# 3rd_eyes.net
KiCad netlist of a schematic drawn in Altium Designer
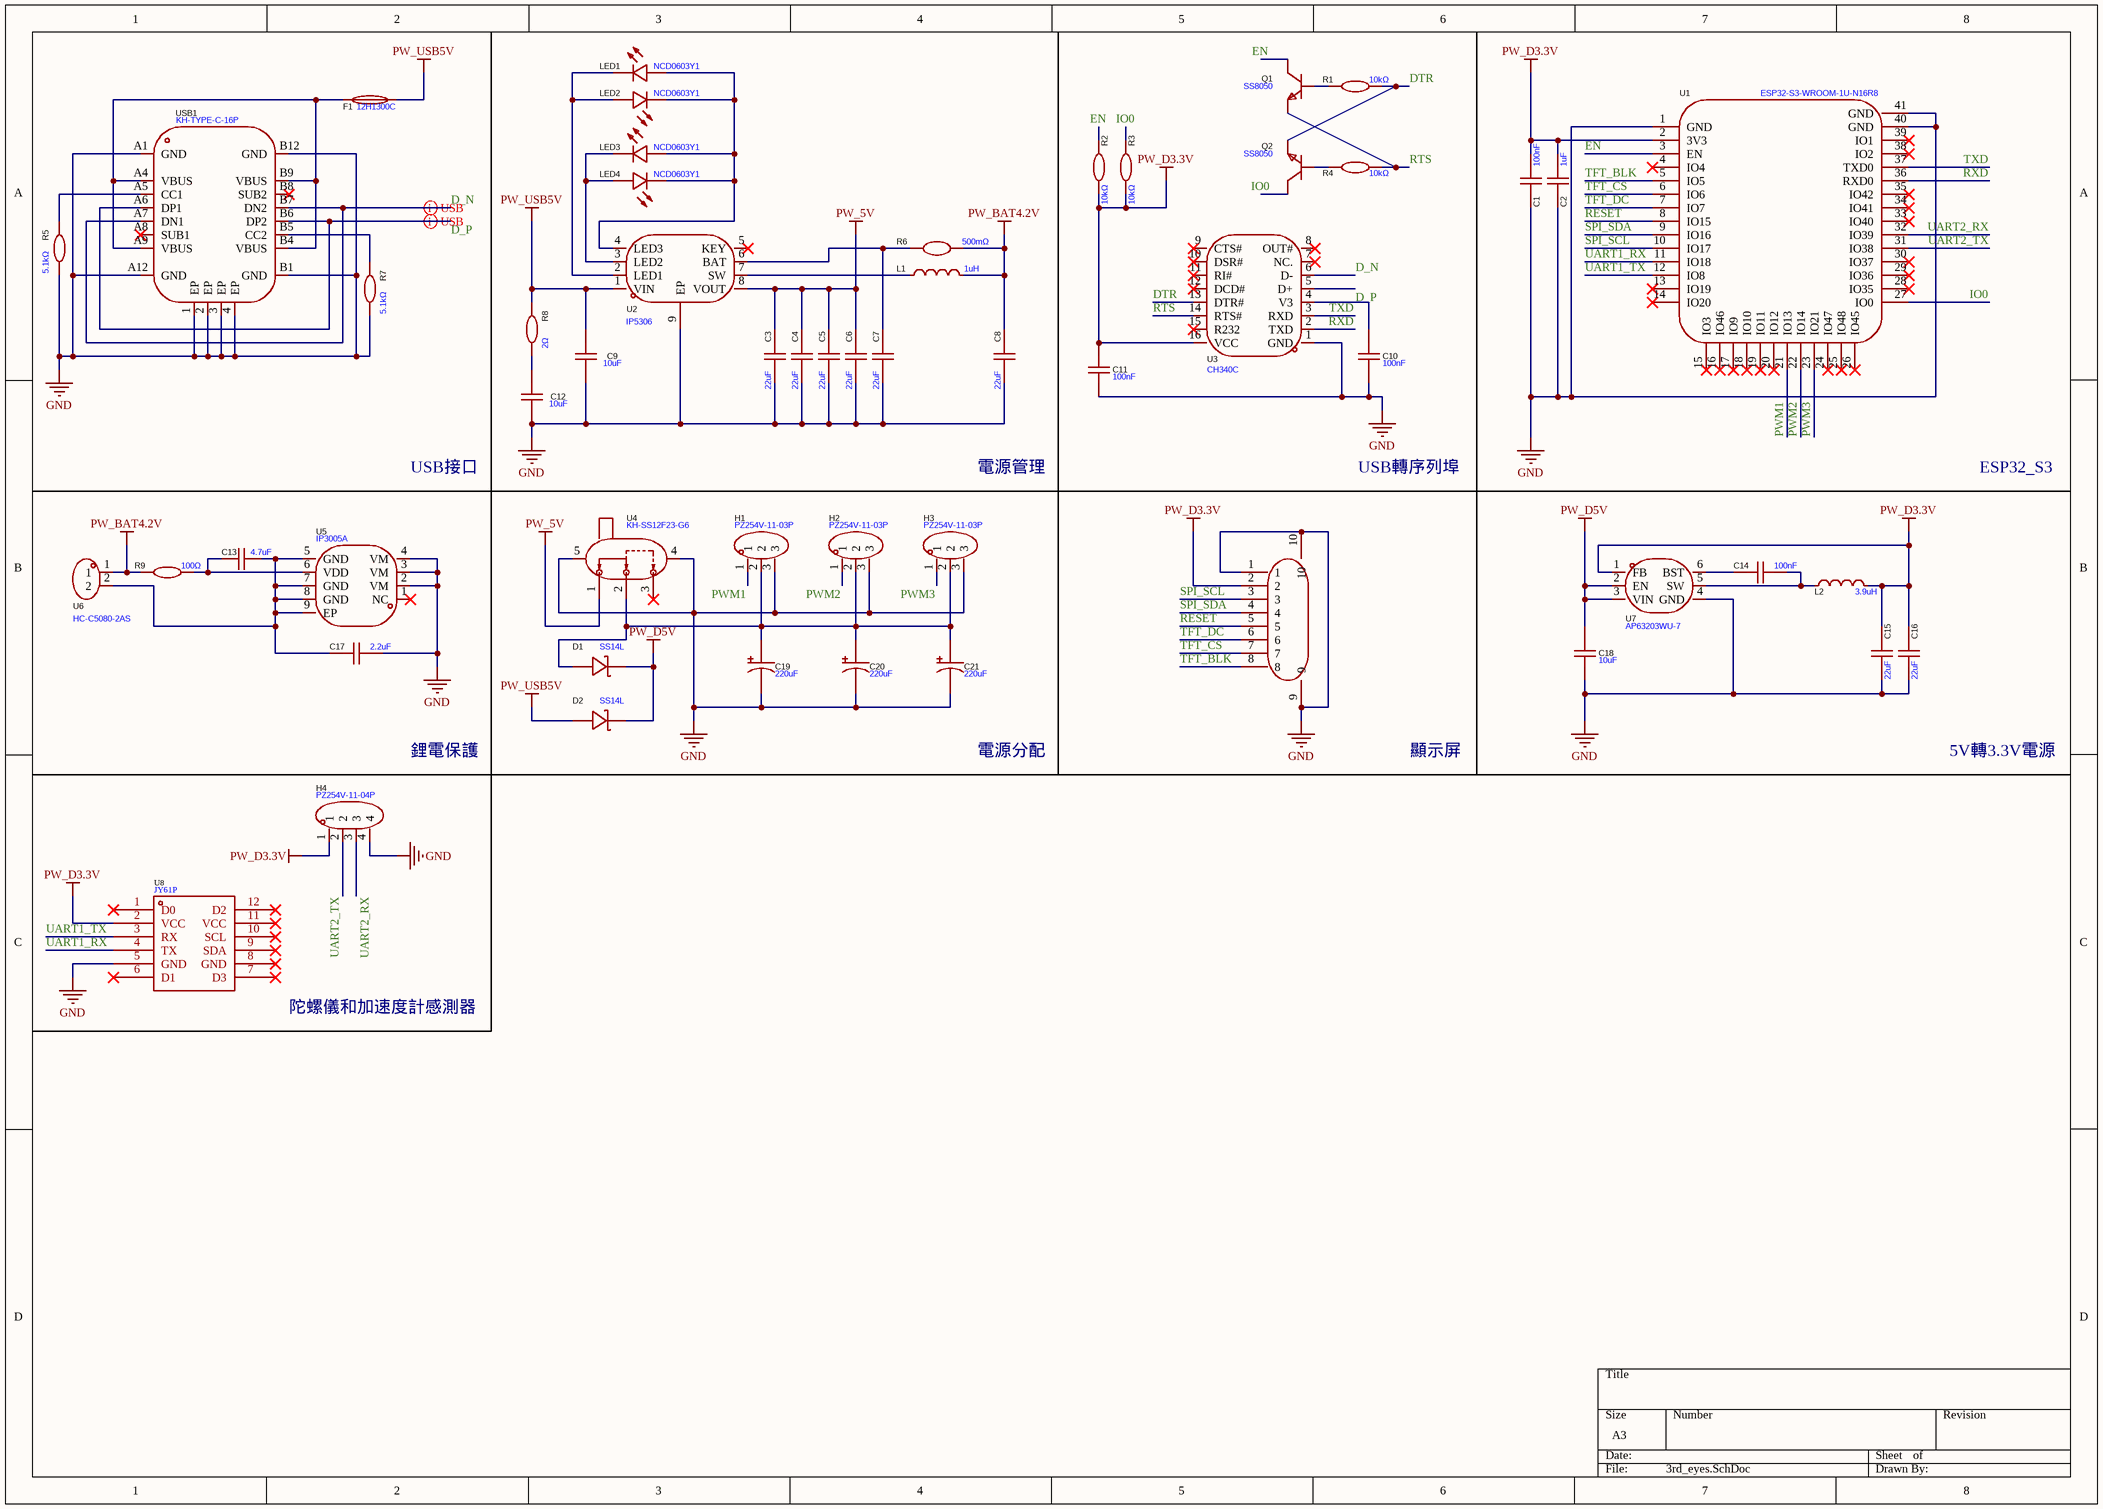
[diagram p0: 3rd_eyes.SchDoc]

(export (version "E")
  (design (tool "Eeschema 10.0.6"))
  (components
    (comp (ref "C1")
      (value "100nF")
      (footprint "C0603")
      (fields
        (field (name "MANUFACTURER") "SAMSUNG(三星)")
        (field (name "MANUFACTURER PART") "CL10B104KB8NNNC")
        (field (name "TOLERANCE") "±10%")
      )
      (libsource (lib "電容") (part "CL10B104KB8NNNC"))
    )
    (comp (ref "C2")
      (value "1uF")
      (footprint "C0603")
      (fields
        (field (name "MANUFACTURER") "SAMSUNG(三星)")
        (field (name "MANUFACTURER PART") "CL10A105KB8NNNC")
        (field (name "TOLERANCE") "±10%")
      )
      (libsource (lib "電容") (part "CL10A105KB8NNNC"))
    )
    (comp (ref "C3")
      (value "22uF")
      (footprint "C0805")
      (fields
        (field (name "MANUFACTURER") "SAMSUNG(三星)")
        (field (name "MANUFACTURER PART") "CL21A226MAQNNNE")
        (field (name "TOLERANCE") "±20%")
      )
      (libsource (lib "電容") (part "CL21A226MAQNNNE"))
    )
    (comp (ref "C4")
      (value "22uF")
      (footprint "C0805")
      (fields
        (field (name "MANUFACTURER") "SAMSUNG(三星)")
        (field (name "MANUFACTURER PART") "CL21A226MAQNNNE")
        (field (name "TOLERANCE") "±20%")
      )
      (libsource (lib "電容") (part "CL21A226MAQNNNE"))
    )
    (comp (ref "C5")
      (value "22uF")
      (footprint "C0805")
      (fields
        (field (name "MANUFACTURER") "SAMSUNG(三星)")
        (field (name "MANUFACTURER PART") "CL21A226MAQNNNE")
        (field (name "TOLERANCE") "±20%")
      )
      (libsource (lib "電容") (part "CL21A226MAQNNNE"))
    )
    (comp (ref "C6")
      (value "22uF")
      (footprint "C0805")
      (fields
        (field (name "MANUFACTURER") "SAMSUNG(三星)")
        (field (name "MANUFACTURER PART") "CL21A226MAQNNNE")
        (field (name "TOLERANCE") "±20%")
      )
      (libsource (lib "電容") (part "CL21A226MAQNNNE"))
    )
    (comp (ref "C7")
      (value "22uF")
      (footprint "C0805")
      (fields
        (field (name "MANUFACTURER") "SAMSUNG(三星)")
        (field (name "MANUFACTURER PART") "CL21A226MAQNNNE")
        (field (name "TOLERANCE") "±20%")
      )
      (libsource (lib "電容") (part "CL21A226MAQNNNE"))
    )
    (comp (ref "C8")
      (value "22uF")
      (footprint "C0805")
      (fields
        (field (name "MANUFACTURER") "SAMSUNG(三星)")
        (field (name "MANUFACTURER PART") "CL21A226MAQNNNE")
        (field (name "TOLERANCE") "±20%")
      )
      (libsource (lib "電容") (part "CL21A226MAQNNNE"))
    )
    (comp (ref "C9")
      (value "10uF")
      (footprint "C0603")
      (fields
        (field (name "MANUFACTURER") "SAMSUNG(三星)")
        (field (name "MANUFACTURER PART") "CL10A106MA8NRNC")
        (field (name "TOLERANCE") "±20%")
      )
      (libsource (lib "電容") (part "CL10A106MA8NRNC"))
    )
    (comp (ref "C10")
      (value "100nF")
      (footprint "C0603")
      (fields
        (field (name "MANUFACTURER") "SAMSUNG(三星)")
        (field (name "MANUFACTURER PART") "CL10B104KB8NNNC")
        (field (name "TOLERANCE") "±10%")
      )
      (libsource (lib "電容") (part "CL10B104KB8NNNC"))
    )
    (comp (ref "C11")
      (value "100nF")
      (footprint "C0603")
      (fields
        (field (name "MANUFACTURER") "SAMSUNG(三星)")
        (field (name "MANUFACTURER PART") "CL10B104KB8NNNC")
        (field (name "TOLERANCE") "±10%")
      )
      (libsource (lib "電容") (part "CL10B104KB8NNNC"))
    )
    (comp (ref "C12")
      (value "10uF")
      (footprint "C0603")
      (fields
        (field (name "MANUFACTURER") "SAMSUNG(三星)")
        (field (name "MANUFACTURER PART") "CL10A106MA8NRNC")
        (field (name "TOLERANCE") "±20%")
      )
      (libsource (lib "電容") (part "CL10A106MA8NRNC"))
    )
    (comp (ref "C13")
      (value "4.7uF")
      (footprint "C0603")
      (fields
        (field (name "MANUFACTURER") "SAMSUNG(三星)")
        (field (name "MANUFACTURER PART") "CL10A475KO8NNNC")
        (field (name "TOLERANCE") "±10%")
      )
      (libsource (lib "電容") (part "CL10A475KO8NNNC"))
    )
    (comp (ref "C14")
      (value "100nF")
      (footprint "C0603")
      (fields
        (field (name "MANUFACTURER") "SAMSUNG(三星)")
        (field (name "MANUFACTURER PART") "CL10B104KB8NNNC")
        (field (name "TOLERANCE") "±10%")
      )
      (libsource (lib "電容") (part "CL10B104KB8NNNC"))
    )
    (comp (ref "C15")
      (value "22uF")
      (footprint "C0805")
      (fields
        (field (name "MANUFACTURER") "SAMSUNG(三星)")
        (field (name "MANUFACTURER PART") "CL21A226MAQNNNE")
        (field (name "TOLERANCE") "±20%")
      )
      (libsource (lib "電容") (part "CL21A226MAQNNNE"))
    )
    (comp (ref "C16")
      (value "22uF")
      (footprint "C0805")
      (fields
        (field (name "MANUFACTURER") "SAMSUNG(三星)")
        (field (name "MANUFACTURER PART") "CL21A226MAQNNNE")
        (field (name "TOLERANCE") "±20%")
      )
      (libsource (lib "電容") (part "CL21A226MAQNNNE"))
    )
    (comp (ref "C17")
      (value "2.2uF")
      (footprint "C0603")
      (fields
        (field (name "MANUFACTURER") "SAMSUNG(三星)")
        (field (name "MANUFACTURER PART") "CL10A225KB8NNNC")
        (field (name "TOLERANCE") "±10%")
      )
      (libsource (lib "電容") (part "CL10A225KB8NNNC"))
    )
    (comp (ref "C18")
      (value "10uF")
      (footprint "C0603")
      (fields
        (field (name "MANUFACTURER") "SAMSUNG(三星)")
        (field (name "MANUFACTURER PART") "CL10A106MA8NRNC")
        (field (name "TOLERANCE") "±20%")
      )
      (libsource (lib "電容") (part "CL10A106MA8NRNC"))
    )
    (comp (ref "C19")
      (value "220uF")
      (footprint "CAP-SMD_BD6.3-L6.6-W6.6-FD-A")
      (fields
        (field (name "MANUFACTURER") "lelon(立隆)")
        (field (name "MANUFACTURER PART") "OVZ221M0JTR-0606")
        (field (name "TOLERANCE") "±20%")
      )
      (libsource (lib "電容") (part "OVZ221M0JTR-0606"))
    )
    (comp (ref "C20")
      (value "220uF")
      (footprint "CAP-SMD_BD6.3-L6.6-W6.6-FD-A")
      (fields
        (field (name "MANUFACTURER") "lelon(立隆)")
        (field (name "MANUFACTURER PART") "OVZ221M0JTR-0606")
        (field (name "TOLERANCE") "±20%")
      )
      (libsource (lib "電容") (part "OVZ221M0JTR-0606"))
    )
    (comp (ref "C21")
      (value "220uF")
      (footprint "CAP-SMD_BD6.3-L6.6-W6.6-FD-A")
      (fields
        (field (name "MANUFACTURER") "lelon(立隆)")
        (field (name "MANUFACTURER PART") "OVZ221M0JTR-0606")
        (field (name "TOLERANCE") "±20%")
      )
      (libsource (lib "電容") (part "OVZ221M0JTR-0606"))
    )
    (comp (ref "D1")
      (value "SS14L")
      (footprint "SOD-123F_L2.8-W1.8-LS3.7-RD")
      (fields (field (name "MANUFACTURER") "Hottech(合科泰)"))
      (libsource (lib "二極管") (part "SS14L"))
    )
    (comp (ref "D2")
      (value "SS14L")
      (footprint "SOD-123F_L2.8-W1.8-LS3.7-RD")
      (fields (field (name "MANUFACTURER") "Hottech(合科泰)"))
      (libsource (lib "二極管") (part "SS14L"))
    )
    (comp (ref "F1")
      (value "12H1300C")
      (footprint "F1206")
      (fields (field (name "MANUFACTURER") "LANSON(良胜)"))
      (libsource (lib "貼片保險絲") (part "12H1300C"))
    )
    (comp (ref "FPC1")
      (value "AFC01-S08FCA-00")
      (footprint "FPC-SMD_P0.50-8P_FGS-XJ-H2.0")
      (fields (field (name "MANUFACTURER") "JS(钜硕电子)"))
      (libsource (lib "針脚") (part "AFC01-S08FCA-00"))
    )
    (comp (ref "H1")
      (value "PZ254V-11-03P")
      (footprint "HDR-TH_3P-P2.54-V-M")
      (fields (field (name "MANUFACTURER") "XFCN(兴飞)"))
      (libsource (lib "針脚") (part "PZ254V-11-03P"))
    )
    (comp (ref "H2")
      (value "PZ254V-11-03P")
      (footprint "HDR-TH_3P-P2.54-V-M")
      (fields (field (name "MANUFACTURER") "XFCN(兴飞)"))
      (libsource (lib "針脚") (part "PZ254V-11-03P"))
    )
    (comp (ref "H3")
      (value "PZ254V-11-03P")
      (footprint "HDR-TH_3P-P2.54-V-M")
      (fields (field (name "MANUFACTURER") "XFCN(兴飞)"))
      (libsource (lib "針脚") (part "PZ254V-11-03P"))
    )
    (comp (ref "H4")
      (value "PZ254V-11-04P")
      (footprint "HDR-TH_4P-P2.54-V-M")
      (fields (field (name "MANUFACTURER") "XFCN(兴飞)"))
      (libsource (lib "針脚") (part "PZ254V-11-04P_C492403"))
    )
    (comp (ref "L1")
      (value "1uH")
      (footprint "IND-SMD_L7.0-W6.6")
      (fields
        (field (name "MANUFACTURER") "cjiang(长江微电)")
        (field (name "MANUFACTURER PART") "FXL0630-1R0-M")
        (field (name "TOLERANCE") "±20%")
      )
      (libsource (lib "電感") (part "FXL0630-1R0-M"))
    )
    (comp (ref "L2")
      (value "3.9uH")
      (footprint "IND-SMD_L4.0-W4.0_FNR40XXS")
      (fields
        (field (name "MANUFACTURER") "cjiang(长江微电)")
        (field (name "MANUFACTURER PART") "FNR4030S3R9MT")
        (field (name "TOLERANCE") "±20%")
      )
      (libsource (lib "電感") (part "FNR4030S3R9MT"))
    )
    (comp (ref "LED1")
      (value "NCD0603Y1")
      (footprint "LED0603-RD")
      (fields (field (name "MANUFACTURER") "国星光电"))
      (libsource (lib "二極管") (part "NCD0603Y1"))
    )
    (comp (ref "LED2")
      (value "NCD0603Y1")
      (footprint "LED0603-RD")
      (fields (field (name "MANUFACTURER") "国星光电"))
      (libsource (lib "二極管") (part "NCD0603Y1"))
    )
    (comp (ref "LED3")
      (value "NCD0603Y1")
      (footprint "LED0603-RD")
      (fields (field (name "MANUFACTURER") "国星光电"))
      (libsource (lib "二極管") (part "NCD0603Y1"))
    )
    (comp (ref "LED4")
      (value "NCD0603Y1")
      (footprint "LED0603-RD")
      (fields (field (name "MANUFACTURER") "国星光电"))
      (libsource (lib "二極管") (part "NCD0603Y1"))
    )
    (comp (ref "Q1")
      (value "SS8050")
      (footprint "SOT-23-3_L2.9-W1.3-P1.90-LS2.4-BR")
      (fields (field (name "MANUFACTURER") "AnBon(安邦)"))
      (libsource (lib "三極管") (part "SS8050_C541705"))
    )
    (comp (ref "Q2")
      (value "SS8050")
      (footprint "SOT-23-3_L2.9-W1.3-P1.90-LS2.4-BR")
      (fields (field (name "MANUFACTURER") "AnBon(安邦)"))
      (libsource (lib "三極管") (part "SS8050_C541705"))
    )
    (comp (ref "R1")
      (value "10kΩ")
      (footprint "R0603")
      (fields
        (field (name "MANUFACTURER") "UNI-ROYAL(厚声)")
        (field (name "MANUFACTURER PART") "0603WAF1002T5E")
        (field (name "TOLERANCE") "±1%")
      )
      (libsource (lib "貼片電組") (part "0603WAF1002T5E"))
    )
    (comp (ref "R2")
      (value "10kΩ")
      (footprint "R0603")
      (fields
        (field (name "MANUFACTURER") "UNI-ROYAL(厚声)")
        (field (name "MANUFACTURER PART") "0603WAF1002T5E")
        (field (name "TOLERANCE") "±1%")
      )
      (libsource (lib "貼片電組") (part "0603WAF1002T5E"))
    )
    (comp (ref "R3")
      (value "10kΩ")
      (footprint "R0603")
      (fields
        (field (name "MANUFACTURER") "UNI-ROYAL(厚声)")
        (field (name "MANUFACTURER PART") "0603WAF1002T5E")
        (field (name "TOLERANCE") "±1%")
      )
      (libsource (lib "貼片電組") (part "0603WAF1002T5E"))
    )
    (comp (ref "R4")
      (value "10kΩ")
      (footprint "R0603")
      (fields
        (field (name "MANUFACTURER") "UNI-ROYAL(厚声)")
        (field (name "MANUFACTURER PART") "0603WAF1002T5E")
        (field (name "TOLERANCE") "±1%")
      )
      (libsource (lib "貼片電組") (part "0603WAF1002T5E"))
    )
    (comp (ref "R5")
      (value "5.1kΩ")
      (footprint "R0603")
      (fields
        (field (name "MANUFACTURER") "UNI-ROYAL(厚声)")
        (field (name "MANUFACTURER PART") "0603WAF5101T5E")
        (field (name "TOLERANCE") "±1%")
      )
      (libsource (lib "貼片電組") (part "0603WAF5101T5E"))
    )
    (comp (ref "R6")
      (value "500mΩ")
      (footprint "R0805")
      (fields
        (field (name "MANUFACTURER") "FOJAN(富捷)")
        (field (name "MANUFACTURER PART") "FRL0805JR500TS")
        (field (name "TOLERANCE") "±5%")
      )
      (libsource (lib "貼片電組") (part "FRL0805JR500TS"))
    )
    (comp (ref "R7")
      (value "5.1kΩ")
      (footprint "R0603")
      (fields
        (field (name "MANUFACTURER") "UNI-ROYAL(厚声)")
        (field (name "MANUFACTURER PART") "0603WAF5101T5E")
        (field (name "TOLERANCE") "±1%")
      )
      (libsource (lib "貼片電組") (part "0603WAF5101T5E"))
    )
    (comp (ref "R8")
      (value "2Ω")
      (footprint "R0603")
      (fields
        (field (name "MANUFACTURER") "UNI-ROYAL(厚声)")
        (field (name "MANUFACTURER PART") "0603WAF200KT5E")
        (field (name "TOLERANCE") "±1%")
      )
      (libsource (lib "貼片電組") (part "0603WAF200KT5E"))
    )
    (comp (ref "R9")
      (value "100Ω")
      (footprint "R0603")
      (fields
        (field (name "MANUFACTURER") "UNI-ROYAL(厚声)")
        (field (name "MANUFACTURER PART") "0603WAF1000T5E")
        (field (name "TOLERANCE") "±1%")
      )
      (libsource (lib "貼片電組") (part "0603WAF1000T5E"))
    )
    (comp (ref "U1")
      (value "ESP32-S3-WROOM-1U-N16R8")
      (footprint "WIRELM-SMD_ESP32-S3-WROOM-1U")
      (fields (field (name "MANUFACTURER") "ESPRESSIF(乐鑫)"))
      (libsource (lib "單片機") (part "ESP32-S3-WROOM-1U-N16R8"))
    )
    (comp (ref "U2")
      (value "IP5306")
      (footprint "ESOP-8_L4.9-W3.9-P1.27-LS6.0-BL-EP")
      (fields (field (name "MANUFACTURER") "INJOINIC(英集芯)"))
      (libsource (lib "芯片") (part "IP5306"))
    )
    (comp (ref "U3")
      (value "CH340C")
      (footprint "SOP-16_L10.0-W3.9-P1.27-LS6.0-BL")
      (fields (field (name "MANUFACTURER") "WCH(南京沁恒)"))
      (libsource (lib "芯片") (part "CH340C"))
    )
    (comp (ref "U4")
      (value "KH-SS12F23-G6")
      (footprint "SW-TH_KH-SS12F23-G6")
      (fields (field (name "MANUFACTURER") "kinghelm(金航标)"))
      (libsource (lib "開關") (part "KH-SS12F23-G6"))
    )
    (comp (ref "U5")
      (value "IP3005A")
      (footprint "ESOP-8_L4.9-W3.9-P1.27-LS6.0-BL-EP")
      (fields (field (name "MANUFACTURER") "INJOINIC(英集芯)"))
      (libsource (lib "芯片") (part "IP3005A"))
    )
    (comp (ref "U6")
      (value "HC-C5080-2AS")
      (footprint "CONN-TH_HC-C5080-2AS")
      (fields (field (name "MANUFACTURER") "HCTL(华灿天禄)"))
      (libsource (lib "針脚") (part "HC-C5080-2AS"))
    )
    (comp (ref "U7")
      (value "AP63203WU-7")
      (footprint "TSOT-26_L2.9-W1.6-P0.95-LS2.8-BL")
      (fields (field (name "MANUFACTURER") "DIODES(美台)"))
      (libsource (lib "芯片") (part "AP63203WU-7"))
    )
    (comp (ref "U8") (value "JY61P") (footprint "JY61P") (libsource (lib "感測器") (part "JY61P")))
    (comp (ref "USB1")
      (value "KH-TYPE-C-16P")
      (footprint "USB-C-SMD_KH-TYPE-C-16P")
      (fields (field (name "MANUFACTURER") "kinghelm(金航标)"))
      (libsource (lib "KH-TYPE-C-16P") (part "KH-TYPE-C-16P"))
    )
  )
  (nets
    (net (code "1") (name "/DTR") (class "Default")
      (node (ref "Q2") (pin "2") (pinfunction "E_2") (pintype "passive"))
      (node (ref "R1") (pin "2") (pinfunction "2_2") (pintype "passive"))
      (node (ref "U3") (pin "13") (pinfunction "DTR#_13") (pintype "passive"))
    )
    (net (code "2") (name "/D_N") (class "Default")
      (node (ref "U3") (pin "6") (pinfunction "D-_6") (pintype "passive"))
      (node (ref "USB1") (pin "A7") (pinfunction "DN1_A7") (pintype "passive"))
      (node (ref "USB1") (pin "B7") (pinfunction "DN2_B7") (pintype "passive"))
    )
    (net (code "3") (name "/D_P") (class "Default")
      (node (ref "U3") (pin "5") (pinfunction "D+_5") (pintype "passive"))
      (node (ref "USB1") (pin "A6") (pinfunction "DP1_A6") (pintype "passive"))
      (node (ref "USB1") (pin "B6") (pinfunction "DP2_B6") (pintype "passive"))
    )
    (net (code "4") (name "/EN") (class "Default")
      (node (ref "Q1") (pin "3") (pinfunction "C_3") (pintype "passive"))
      (node (ref "R2") (pin "1") (pinfunction "1_1") (pintype "passive"))
      (node (ref "U1") (pin "3") (pinfunction "EN_3") (pintype "passive"))
    )
    (net (code "5") (name "/IO0") (class "Default")
      (node (ref "Q2") (pin "3") (pinfunction "C_3") (pintype "passive"))
      (node (ref "R3") (pin "1") (pinfunction "1_1") (pintype "passive"))
      (node (ref "U1") (pin "27") (pinfunction "IO0_27") (pintype "passive"))
    )
    (net (code "6") (name "/PWM1") (class "Default")
      (node (ref "H1") (pin "1") (pinfunction "1_1") (pintype "passive"))
      (node (ref "U1") (pin "21") (pinfunction "IO13_21") (pintype "passive"))
    )
    (net (code "7") (name "/PWM2") (class "Default")
      (node (ref "H2") (pin "1") (pinfunction "1_1") (pintype "passive"))
      (node (ref "U1") (pin "22") (pinfunction "IO14_22") (pintype "passive"))
    )
    (net (code "8") (name "/PWM3") (class "Default")
      (node (ref "H3") (pin "1") (pinfunction "1_1") (pintype "passive"))
      (node (ref "U1") (pin "23") (pinfunction "IO21_23") (pintype "passive"))
    )
    (net (code "9") (name "/RESET") (class "Default")
      (node (ref "FPC1") (pin "5") (pinfunction "5_5") (pintype "passive"))
      (node (ref "U1") (pin "8") (pinfunction "IO15_8") (pintype "passive"))
    )
    (net (code "10") (name "/RTS") (class "Default")
      (node (ref "Q1") (pin "2") (pinfunction "E_2") (pintype "passive"))
      (node (ref "R4") (pin "2") (pinfunction "2_2") (pintype "passive"))
      (node (ref "U3") (pin "14") (pinfunction "RTS#_14") (pintype "passive"))
    )
    (net (code "11") (name "/RXD") (class "Default")
      (node (ref "U1") (pin "36") (pinfunction "RXD0_36") (pintype "passive"))
      (node (ref "U3") (pin "2") (pinfunction "TXD_2") (pintype "passive"))
    )
    (net (code "12") (name "/SPI_SCL") (class "Default")
      (node (ref "FPC1") (pin "3") (pinfunction "3_3") (pintype "passive"))
      (node (ref "U1") (pin "10") (pinfunction "IO17_10") (pintype "passive"))
    )
    (net (code "13") (name "/SPI_SDA") (class "Default")
      (node (ref "FPC1") (pin "4") (pinfunction "4_4") (pintype "passive"))
      (node (ref "U1") (pin "9") (pinfunction "IO16_9") (pintype "passive"))
    )
    (net (code "14") (name "/TFT_BLK") (class "Default")
      (node (ref "FPC1") (pin "8") (pinfunction "8_8") (pintype "passive"))
      (node (ref "U1") (pin "5") (pinfunction "IO5_5") (pintype "passive"))
    )
    (net (code "15") (name "/TFT_CS") (class "Default")
      (node (ref "FPC1") (pin "7") (pinfunction "7_7") (pintype "passive"))
      (node (ref "U1") (pin "6") (pinfunction "IO6_6") (pintype "passive"))
    )
    (net (code "16") (name "/TFT_DC") (class "Default")
      (node (ref "FPC1") (pin "6") (pinfunction "6_6") (pintype "passive"))
      (node (ref "U1") (pin "7") (pinfunction "IO7_7") (pintype "passive"))
    )
    (net (code "17") (name "/TXD") (class "Default")
      (node (ref "U1") (pin "37") (pinfunction "TXD0_37") (pintype "passive"))
      (node (ref "U3") (pin "3") (pinfunction "RXD_3") (pintype "passive"))
    )
    (net (code "18") (name "/UART1_RX") (class "Default")
      (node (ref "U1") (pin "11") (pinfunction "IO18_11") (pintype "passive"))
      (node (ref "U8") (pin "4") (pinfunction "TX_4") (pintype "passive"))
    )
    (net (code "19") (name "/UART1_TX") (class "Default")
      (node (ref "U1") (pin "12") (pinfunction "IO8_12") (pintype "passive"))
      (node (ref "U8") (pin "3") (pinfunction "RX_3") (pintype "passive"))
    )
    (net (code "20") (name "/UART2_RX") (class "Default")
      (node (ref "H4") (pin "3") (pinfunction "3_3") (pintype "passive"))
      (node (ref "U1") (pin "32") (pinfunction "IO39_32") (pintype "passive"))
    )
    (net (code "21") (name "/UART2_TX") (class "Default")
      (node (ref "H4") (pin "2") (pinfunction "2_2") (pintype "passive"))
      (node (ref "U1") (pin "31") (pinfunction "IO38_31") (pintype "passive"))
    )
    (net (code "22") (name "GND") (class "Default")
      (node (ref "C1") (pin "1") (pinfunction "1_1") (pintype "passive"))
      (node (ref "C10") (pin "1") (pinfunction "1_1") (pintype "passive"))
      (node (ref "C11") (pin "1") (pinfunction "1_1") (pintype "passive"))
      (node (ref "C12") (pin "1") (pinfunction "1_1") (pintype "passive"))
      (node (ref "C15") (pin "2") (pinfunction "2_2") (pintype "passive"))
      (node (ref "C16") (pin "2") (pinfunction "2_2") (pintype "passive"))
      (node (ref "C17") (pin "2") (pinfunction "2_2") (pintype "passive"))
      (node (ref "C18") (pin "1") (pinfunction "1_1") (pintype "passive"))
      (node (ref "C19") (pin "2") (pinfunction "2_2") (pintype "passive"))
      (node (ref "C2") (pin "1") (pinfunction "1_1") (pintype "passive"))
      (node (ref "C20") (pin "2") (pinfunction "2_2") (pintype "passive"))
      (node (ref "C21") (pin "2") (pinfunction "2_2") (pintype "passive"))
      (node (ref "C3") (pin "1") (pinfunction "1_1") (pintype "passive"))
      (node (ref "C4") (pin "1") (pinfunction "1_1") (pintype "passive"))
      (node (ref "C5") (pin "1") (pinfunction "1_1") (pintype "passive"))
      (node (ref "C6") (pin "1") (pinfunction "1_1") (pintype "passive"))
      (node (ref "C7") (pin "1") (pinfunction "1_1") (pintype "passive"))
      (node (ref "C8") (pin "1") (pinfunction "1_1") (pintype "passive"))
      (node (ref "C9") (pin "1") (pinfunction "1_1") (pintype "passive"))
      (node (ref "FPC1") (pin "1") (pinfunction "1_1") (pintype "passive"))
      (node (ref "FPC1") (pin "10") (pinfunction "10_10") (pintype "passive"))
      (node (ref "FPC1") (pin "9") (pinfunction "9_9") (pintype "passive"))
      (node (ref "H1") (pin "3") (pinfunction "3_3") (pintype "passive"))
      (node (ref "H2") (pin "3") (pinfunction "3_3") (pintype "passive"))
      (node (ref "H3") (pin "3") (pinfunction "3_3") (pintype "passive"))
      (node (ref "H4") (pin "4") (pinfunction "4_4") (pintype "passive"))
      (node (ref "R5") (pin "2") (pinfunction "2_2") (pintype "passive"))
      (node (ref "R7") (pin "2") (pinfunction "2_2") (pintype "passive"))
      (node (ref "U1") (pin "1") (pinfunction "GND_1") (pintype "passive"))
      (node (ref "U1") (pin "40") (pinfunction "GND_40") (pintype "passive"))
      (node (ref "U1") (pin "41") (pinfunction "GND_41") (pintype "passive"))
      (node (ref "U2") (pin "9") (pinfunction "EP_9") (pintype "passive"))
      (node (ref "U3") (pin "1") (pinfunction "GND_1") (pintype "passive"))
      (node (ref "U4") (pin "4") (pinfunction "4_4") (pintype "passive"))
      (node (ref "U4") (pin "5") (pinfunction "5_5") (pintype "passive"))
      (node (ref "U5") (pin "2") (pinfunction "VM_2") (pintype "passive"))
      (node (ref "U5") (pin "3") (pinfunction "VM_3") (pintype "passive"))
      (node (ref "U5") (pin "4") (pinfunction "VM_4") (pintype "passive"))
      (node (ref "U7") (pin "4") (pinfunction "GND_4") (pintype "passive"))
      (node (ref "U8") (pin "5") (pinfunction "GND_5") (pintype "passive"))
      (node (ref "USB1") (pin "1") (pinfunction "EP_1") (pintype "passive"))
      (node (ref "USB1") (pin "2") (pinfunction "EP_2") (pintype "passive"))
      (node (ref "USB1") (pin "3") (pinfunction "EP_3") (pintype "passive"))
      (node (ref "USB1") (pin "4") (pinfunction "EP_4") (pintype "passive"))
      (node (ref "USB1") (pin "A1") (pinfunction "GND_A1") (pintype "passive"))
      (node (ref "USB1") (pin "A12") (pinfunction "GND_A12") (pintype "passive"))
      (node (ref "USB1") (pin "B1") (pinfunction "GND_B1") (pintype "passive"))
      (node (ref "USB1") (pin "B12") (pinfunction "GND_B12") (pintype "passive"))
    )
    (net (code "23") (name "Net-(C12-Pad2)") (class "Default")
      (node (ref "C12") (pin "2") (pinfunction "2_2") (pintype "passive"))
      (node (ref "R8") (pin "2") (pinfunction "2_2") (pintype "passive"))
    )
    (net (code "24") (name "Net-(D1-A)") (class "Default")
      (node (ref "C19") (pin "1") (pinfunction "1_1") (pintype "passive"))
      (node (ref "C20") (pin "1") (pinfunction "1_1") (pintype "passive"))
      (node (ref "C21") (pin "1") (pinfunction "1_1") (pintype "passive"))
      (node (ref "D1") (pin "2") (pinfunction "A_2") (pintype "passive"))
      (node (ref "H1") (pin "2") (pinfunction "2_2") (pintype "passive"))
      (node (ref "H2") (pin "2") (pinfunction "2_2") (pintype "passive"))
      (node (ref "H3") (pin "2") (pinfunction "2_2") (pintype "passive"))
      (node (ref "U4") (pin "2") (pinfunction "2_2") (pintype "passive"))
    )
    (net (code "25") (name "Net-(F1-Pad1)") (class "Default")
      (node (ref "F1") (pin "1") (pinfunction "1_1") (pintype "passive"))
      (node (ref "USB1") (pin "A4") (pinfunction "VBUS_A4") (pintype "passive"))
      (node (ref "USB1") (pin "A9") (pinfunction "VBUS_A9") (pintype "passive"))
      (node (ref "USB1") (pin "B4") (pinfunction "VBUS_B4") (pintype "passive"))
      (node (ref "USB1") (pin "B9") (pinfunction "VBUS_B9") (pintype "passive"))
    )
    (net (code "26") (name "Net-(LED1-A)") (class "Default")
      (node (ref "LED1") (pin "2") (pinfunction "A_2") (pintype "passive"))
      (node (ref "LED2") (pin "1") (pinfunction "K_1") (pintype "passive"))
      (node (ref "LED3") (pin "2") (pinfunction "A_2") (pintype "passive"))
      (node (ref "LED4") (pin "1") (pinfunction "K_1") (pintype "passive"))
      (node (ref "U2") (pin "4") (pinfunction "LED3_4") (pintype "passive"))
    )
    (net (code "27") (name "Net-(LED1-K)") (class "Default")
      (node (ref "LED1") (pin "1") (pinfunction "K_1") (pintype "passive"))
      (node (ref "LED2") (pin "2") (pinfunction "A_2") (pintype "passive"))
      (node (ref "U2") (pin "2") (pinfunction "LED1_2") (pintype "passive"))
    )
    (net (code "28") (name "Net-(LED3-K)") (class "Default")
      (node (ref "LED3") (pin "1") (pinfunction "K_1") (pintype "passive"))
      (node (ref "LED4") (pin "2") (pinfunction "A_2") (pintype "passive"))
      (node (ref "U2") (pin "3") (pinfunction "LED2_3") (pintype "passive"))
    )
    (net (code "29") (name "Net-(Q1-B)") (class "Default")
      (node (ref "Q1") (pin "1") (pinfunction "B_1") (pintype "passive"))
      (node (ref "R1") (pin "1") (pinfunction "1_1") (pintype "passive"))
    )
    (net (code "30") (name "Net-(Q2-B)") (class "Default")
      (node (ref "Q2") (pin "1") (pinfunction "B_1") (pintype "passive"))
      (node (ref "R4") (pin "1") (pinfunction "1_1") (pintype "passive"))
    )
    (net (code "31") (name "Net-(U2-BAT)") (class "Default")
      (node (ref "C7") (pin "2") (pinfunction "2_2") (pintype "passive"))
      (node (ref "R6") (pin "1") (pinfunction "1_1") (pintype "passive"))
      (node (ref "U2") (pin "6") (pinfunction "BAT_6") (pintype "passive"))
    )
    (net (code "32") (name "Net-(U2-SW)") (class "Default")
      (node (ref "L1") (pin "1") (pinfunction "1_1") (pintype "passive"))
      (node (ref "U2") (pin "7") (pinfunction "SW_7") (pintype "passive"))
    )
    (net (code "33") (name "Net-(U3-V3)") (class "Default")
      (node (ref "C10") (pin "2") (pinfunction "2_2") (pintype "passive"))
      (node (ref "U3") (pin "4") (pinfunction "V3_4") (pintype "passive"))
    )
    (net (code "34") (name "Net-(U5-EP)") (class "Default")
      (node (ref "C13") (pin "2") (pinfunction "2_2") (pintype "passive"))
      (node (ref "C17") (pin "1") (pinfunction "1_1") (pintype "passive"))
      (node (ref "U5") (pin "5") (pinfunction "GND_5") (pintype "passive"))
      (node (ref "U5") (pin "7") (pinfunction "GND_7") (pintype "passive"))
      (node (ref "U5") (pin "8") (pinfunction "GND_8") (pintype "passive"))
      (node (ref "U5") (pin "9") (pinfunction "EP_9") (pintype "passive"))
      (node (ref "U6") (pin "2") (pinfunction "2_2") (pintype "passive"))
    )
    (net (code "35") (name "Net-(U5-VDD)") (class "Default")
      (node (ref "C13") (pin "1") (pinfunction "1_1") (pintype "passive"))
      (node (ref "R9") (pin "2") (pinfunction "2_2") (pintype "passive"))
      (node (ref "U5") (pin "6") (pinfunction "VDD_6") (pintype "passive"))
    )
    (net (code "36") (name "Net-(U7-BST)") (class "Default")
      (node (ref "C14") (pin "1") (pinfunction "1_1") (pintype "passive"))
      (node (ref "U7") (pin "6") (pinfunction "BST_6") (pintype "passive"))
    )
    (net (code "37") (name "Net-(U7-SW)") (class "Default")
      (node (ref "C14") (pin "2") (pinfunction "2_2") (pintype "passive"))
      (node (ref "L2") (pin "1") (pinfunction "1_1") (pintype "passive"))
      (node (ref "U7") (pin "5") (pinfunction "SW_5") (pintype "passive"))
    )
    (net (code "38") (name "Net-(USB1-CC1)") (class "Default")
      (node (ref "R5") (pin "1") (pinfunction "1_1") (pintype "passive"))
      (node (ref "USB1") (pin "A5") (pinfunction "CC1_A5") (pintype "passive"))
    )
    (net (code "39") (name "Net-(USB1-CC2)") (class "Default")
      (node (ref "R7") (pin "1") (pinfunction "1_1") (pintype "passive"))
      (node (ref "USB1") (pin "B5") (pinfunction "CC2_B5") (pintype "passive"))
    )
    (net (code "40") (name "PW_5V") (class "Default")
      (node (ref "C3") (pin "2") (pinfunction "2_2") (pintype "passive"))
      (node (ref "C4") (pin "2") (pinfunction "2_2") (pintype "passive"))
      (node (ref "C5") (pin "2") (pinfunction "2_2") (pintype "passive"))
      (node (ref "C6") (pin "2") (pinfunction "2_2") (pintype "passive"))
      (node (ref "U2") (pin "8") (pinfunction "VOUT_8") (pintype "passive"))
      (node (ref "U4") (pin "1") (pinfunction "1_1") (pintype "passive"))
    )
    (net (code "41") (name "PW_BAT4.2V") (class "Default")
      (node (ref "C8") (pin "2") (pinfunction "2_2") (pintype "passive"))
      (node (ref "L1") (pin "2") (pinfunction "2_2") (pintype "passive"))
      (node (ref "R6") (pin "2") (pinfunction "2_2") (pintype "passive"))
      (node (ref "R9") (pin "1") (pinfunction "1_1") (pintype "passive"))
      (node (ref "U6") (pin "1") (pinfunction "1_1") (pintype "passive"))
    )
    (net (code "42") (name "PW_D3.3V") (class "Default")
      (node (ref "C1") (pin "2") (pinfunction "2_2") (pintype "passive"))
      (node (ref "C11") (pin "2") (pinfunction "2_2") (pintype "passive"))
      (node (ref "C15") (pin "1") (pinfunction "1_1") (pintype "passive"))
      (node (ref "C16") (pin "1") (pinfunction "1_1") (pintype "passive"))
      (node (ref "C2") (pin "2") (pinfunction "2_2") (pintype "passive"))
      (node (ref "FPC1") (pin "2") (pinfunction "2_2") (pintype "passive"))
      (node (ref "H4") (pin "1") (pinfunction "1_1") (pintype "passive"))
      (node (ref "L2") (pin "2") (pinfunction "2_2") (pintype "passive"))
      (node (ref "R2") (pin "2") (pinfunction "2_2") (pintype "passive"))
      (node (ref "R3") (pin "2") (pinfunction "2_2") (pintype "passive"))
      (node (ref "U1") (pin "2") (pinfunction "3V3_2") (pintype "passive"))
      (node (ref "U3") (pin "16") (pinfunction "VCC_16") (pintype "passive"))
      (node (ref "U7") (pin "1") (pinfunction "FB_1") (pintype "passive"))
      (node (ref "U8") (pin "2") (pinfunction "VCC_2") (pintype "passive"))
    )
    (net (code "43") (name "PW_D5V") (class "Default")
      (node (ref "C18") (pin "2") (pinfunction "2_2") (pintype "passive"))
      (node (ref "D1") (pin "1") (pinfunction "K_1") (pintype "passive"))
      (node (ref "D2") (pin "1") (pinfunction "K_1") (pintype "passive"))
      (node (ref "U7") (pin "2") (pinfunction "EN_2") (pintype "passive"))
      (node (ref "U7") (pin "3") (pinfunction "VIN_3") (pintype "passive"))
    )
    (net (code "44") (name "PW_USB5V") (class "Default")
      (node (ref "C9") (pin "2") (pinfunction "2_2") (pintype "passive"))
      (node (ref "D2") (pin "2") (pinfunction "A_2") (pintype "passive"))
      (node (ref "F1") (pin "2") (pinfunction "2_2") (pintype "passive"))
      (node (ref "R8") (pin "1") (pinfunction "1_1") (pintype "passive"))
      (node (ref "U2") (pin "1") (pinfunction "VIN_1") (pintype "passive"))
    )
    (net (code "45") (name "unconnected-(U1-IO1-Pad39)") (class "Default")
      (node (ref "U1") (pin "39") (pinfunction "IO1_39") (pintype "passive+no_connect"))
    )
    (net (code "46") (name "unconnected-(U1-IO2-Pad38)") (class "Default")
      (node (ref "U1") (pin "38") (pinfunction "IO2_38") (pintype "passive+no_connect"))
    )
    (net (code "47") (name "unconnected-(U1-IO3-Pad15)") (class "Default")
      (node (ref "U1") (pin "15") (pinfunction "IO3_15") (pintype "passive+no_connect"))
    )
    (net (code "48") (name "unconnected-(U1-IO4-Pad4)") (class "Default")
      (node (ref "U1") (pin "4") (pinfunction "IO4_4") (pintype "passive+no_connect"))
    )
    (net (code "49") (name "unconnected-(U1-IO9-Pad17)") (class "Default")
      (node (ref "U1") (pin "17") (pinfunction "IO9_17") (pintype "passive+no_connect"))
    )
    (net (code "50") (name "unconnected-(U1-IO10-Pad18)") (class "Default")
      (node (ref "U1") (pin "18") (pinfunction "IO10_18") (pintype "passive+no_connect"))
    )
    (net (code "51") (name "unconnected-(U1-IO11-Pad19)") (class "Default")
      (node (ref "U1") (pin "19") (pinfunction "IO11_19") (pintype "passive+no_connect"))
    )
    (net (code "52") (name "unconnected-(U1-IO12-Pad20)") (class "Default")
      (node (ref "U1") (pin "20") (pinfunction "IO12_20") (pintype "passive+no_connect"))
    )
    (net (code "53") (name "unconnected-(U1-IO19-Pad13)") (class "Default")
      (node (ref "U1") (pin "13") (pinfunction "IO19_13") (pintype "passive+no_connect"))
    )
    (net (code "54") (name "unconnected-(U1-IO20-Pad14)") (class "Default")
      (node (ref "U1") (pin "14") (pinfunction "IO20_14") (pintype "passive+no_connect"))
    )
    (net (code "55") (name "unconnected-(U1-IO35-Pad28)") (class "Default")
      (node (ref "U1") (pin "28") (pinfunction "IO35_28") (pintype "passive+no_connect"))
    )
    (net (code "56") (name "unconnected-(U1-IO36-Pad29)") (class "Default")
      (node (ref "U1") (pin "29") (pinfunction "IO36_29") (pintype "passive+no_connect"))
    )
    (net (code "57") (name "unconnected-(U1-IO37-Pad30)") (class "Default")
      (node (ref "U1") (pin "30") (pinfunction "IO37_30") (pintype "passive+no_connect"))
    )
    (net (code "58") (name "unconnected-(U1-IO40-Pad33)") (class "Default")
      (node (ref "U1") (pin "33") (pinfunction "IO40_33") (pintype "passive+no_connect"))
    )
    (net (code "59") (name "unconnected-(U1-IO41-Pad34)") (class "Default")
      (node (ref "U1") (pin "34") (pinfunction "IO41_34") (pintype "passive+no_connect"))
    )
    (net (code "60") (name "unconnected-(U1-IO42-Pad35)") (class "Default")
      (node (ref "U1") (pin "35") (pinfunction "IO42_35") (pintype "passive+no_connect"))
    )
    (net (code "61") (name "unconnected-(U1-IO45-Pad26)") (class "Default")
      (node (ref "U1") (pin "26") (pinfunction "IO45_26") (pintype "passive+no_connect"))
    )
    (net (code "62") (name "unconnected-(U1-IO46-Pad16)") (class "Default")
      (node (ref "U1") (pin "16") (pinfunction "IO46_16") (pintype "passive+no_connect"))
    )
    (net (code "63") (name "unconnected-(U1-IO47-Pad24)") (class "Default")
      (node (ref "U1") (pin "24") (pinfunction "IO47_24") (pintype "passive+no_connect"))
    )
    (net (code "64") (name "unconnected-(U1-IO48-Pad25)") (class "Default")
      (node (ref "U1") (pin "25") (pinfunction "IO48_25") (pintype "passive+no_connect"))
    )
    (net (code "65") (name "unconnected-(U2-KEY-Pad5)") (class "Default")
      (node (ref "U2") (pin "5") (pinfunction "KEY_5") (pintype "passive+no_connect"))
    )
    (net (code "66") (name "unconnected-(U3-CTS#-Pad9)") (class "Default")
      (node (ref "U3") (pin "9") (pinfunction "CTS#_9") (pintype "passive+no_connect"))
    )
    (net (code "67") (name "unconnected-(U3-DCD#-Pad12)") (class "Default")
      (node (ref "U3") (pin "12") (pinfunction "DCD#_12") (pintype "passive+no_connect"))
    )
    (net (code "68") (name "unconnected-(U3-DSR#-Pad10)") (class "Default")
      (node (ref "U3") (pin "10") (pinfunction "DSR#_10") (pintype "passive+no_connect"))
    )
    (net (code "69") (name "unconnected-(U3-NC.-Pad7)") (class "Default")
      (node (ref "U3") (pin "7") (pinfunction "NC._7") (pintype "passive+no_connect"))
    )
    (net (code "70") (name "unconnected-(U3-OUT#-Pad8)") (class "Default")
      (node (ref "U3") (pin "8") (pinfunction "OUT#_8") (pintype "passive+no_connect"))
    )
    (net (code "71") (name "unconnected-(U3-R232-Pad15)") (class "Default")
      (node (ref "U3") (pin "15") (pinfunction "R232_15") (pintype "passive+no_connect"))
    )
    (net (code "72") (name "unconnected-(U3-RI#-Pad11)") (class "Default")
      (node (ref "U3") (pin "11") (pinfunction "RI#_11") (pintype "passive+no_connect"))
    )
    (net (code "73") (name "unconnected-(U4-Pad3)") (class "Default")
      (node (ref "U4") (pin "3") (pinfunction "3_3") (pintype "passive+no_connect"))
    )
    (net (code "74") (name "unconnected-(U5-NC-Pad1)") (class "Default")
      (node (ref "U5") (pin "1") (pinfunction "NC_1") (pintype "passive+no_connect"))
    )
    (net (code "75") (name "unconnected-(U8-D0-Pad1)") (class "Default")
      (node (ref "U8") (pin "1") (pinfunction "D0_1") (pintype "passive+no_connect"))
    )
    (net (code "76") (name "unconnected-(U8-D1-Pad6)") (class "Default")
      (node (ref "U8") (pin "6") (pinfunction "D1_6") (pintype "passive+no_connect"))
    )
    (net (code "77") (name "unconnected-(U8-D2-Pad12)") (class "Default")
      (node (ref "U8") (pin "12") (pinfunction "D2_12") (pintype "passive+no_connect"))
    )
    (net (code "78") (name "unconnected-(U8-D3-Pad7)") (class "Default")
      (node (ref "U8") (pin "7") (pinfunction "D3_7") (pintype "passive+no_connect"))
    )
    (net (code "79") (name "unconnected-(U8-GND-Pad8)") (class "Default")
      (node (ref "U8") (pin "8") (pinfunction "GND_8") (pintype "passive+no_connect"))
    )
    (net (code "80") (name "unconnected-(U8-SCL-Pad10)") (class "Default")
      (node (ref "U8") (pin "10") (pinfunction "SCL_10") (pintype "passive+no_connect"))
    )
    (net (code "81") (name "unconnected-(U8-SDA-Pad9)") (class "Default")
      (node (ref "U8") (pin "9") (pinfunction "SDA_9") (pintype "passive+no_connect"))
    )
    (net (code "82") (name "unconnected-(U8-VCC-Pad11)") (class "Default")
      (node (ref "U8") (pin "11") (pinfunction "VCC_11") (pintype "passive+no_connect"))
    )
    (net (code "83") (name "unconnected-(USB1-SUB1-PadA8)") (class "Default")
      (node (ref "USB1") (pin "A8") (pinfunction "SUB1_A8") (pintype "passive+no_connect"))
    )
    (net (code "84") (name "unconnected-(USB1-SUB2-PadB8)") (class "Default")
      (node (ref "USB1") (pin "B8") (pinfunction "SUB2_B8") (pintype "passive+no_connect"))
    )
  )
)
